# Peripherals.net
KiCad netlist of a schematic drawn in Altium Designer
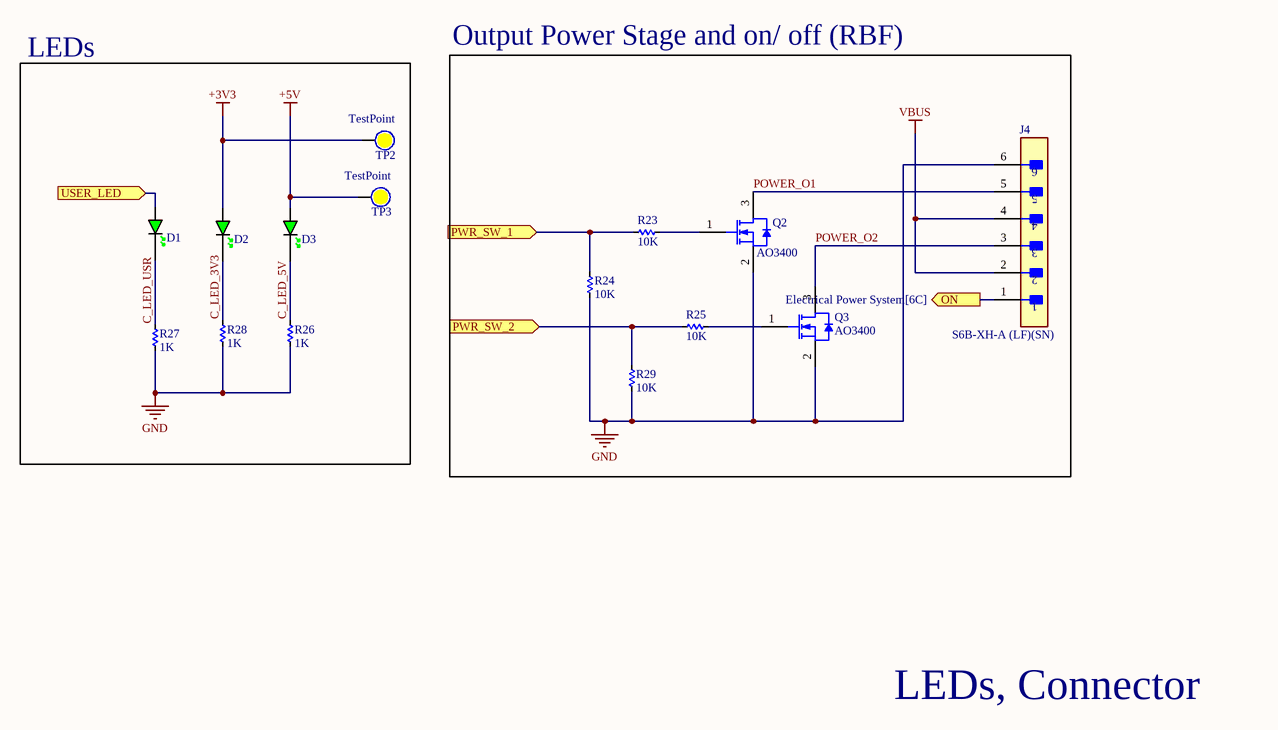
[diagram p0: Peripherals.SchDoc]

(export (version "E")
  (design (tool "Eeschema 10.0.6"))
  (components
    (comp (ref "D1")
      (value "GREEN")
      (footprint "LED_0603_GREEN")
      (description "LED 0603 GREEN SMD")
      (libsource (lib "Schematic-Lib-PhilsLab") (part "LED_0603_GREEN"))
    )
    (comp (ref "D2")
      (value "GREEN")
      (footprint "LED_0603_GREEN")
      (description "LED 0603 GREEN SMD")
      (libsource (lib "Schematic-Lib-PhilsLab") (part "LED_0603_GREEN"))
    )
    (comp (ref "D3")
      (value "GREEN")
      (footprint "LED_0603_GREEN")
      (description "LED 0603 GREEN SMD")
      (libsource (lib "Schematic-Lib-PhilsLab") (part "LED_0603_GREEN"))
    )
    (comp (ref "J4")
      (value "S6B-XH-A (LF)(SN)")
      (footprint "FP-S6B-XH-A_LF_SN-MFG")
      (description "CONN HEADER R/A 6POS 2.5MM")
      (libsource (lib "Altium Content Vault") (part "f2cb566baf1c37ab5a3b8e90bbeafd6"))
    )
    (comp (ref "Q2")
      (value "AO3400")
      (footprint "AO-SOT23-3_V")
      (description "N-channel Enhancement Mode Field-Effect Transistor; 5.8A/30V")
      (fields (field (name "MANUFACTURER") "Alpha and Omega"))
      (libsource (lib "Altium Content Vault") (part "AO-NEMOS-G1S2D3-3"))
    )
    (comp (ref "Q3")
      (value "AO3400")
      (footprint "AO-SOT23-3_V")
      (description "N-channel Enhancement Mode Field-Effect Transistor; 5.8A/30V")
      (fields (field (name "MANUFACTURER") "Alpha and Omega"))
      (libsource (lib "Altium Content Vault") (part "AO-NEMOS-G1S2D3-3"))
    )
    (comp (ref "R23")
      (value "10K")
      (footprint "RES-SMD-0805")
      (description "SMD")
      (fields
        (field (name "MANUFACTURER") "Generic Components")
        (field (name "PUBLISHER") "Altium Hobart Technology Centre")
      )
      (libsource (lib "Sang_library") (part "Res SMD"))
    )
    (comp (ref "R24")
      (value "10K")
      (footprint "RES-SMD-0805")
      (description "SMD")
      (fields
        (field (name "MANUFACTURER") "Generic Components")
        (field (name "PUBLISHER") "Altium Hobart Technology Centre")
      )
      (libsource (lib "Sang_library") (part "Res SMD"))
    )
    (comp (ref "R25")
      (value "10K")
      (footprint "RES-SMD-0805")
      (description "SMD")
      (fields
        (field (name "MANUFACTURER") "Generic Components")
        (field (name "PUBLISHER") "Altium Hobart Technology Centre")
      )
      (libsource (lib "Sang_library") (part "Res SMD"))
    )
    (comp (ref "R26")
      (value "1K")
      (footprint "RES-SMD-0805")
      (description "SMD")
      (fields
        (field (name "MANUFACTURER") "Generic Components")
        (field (name "PUBLISHER") "Altium Hobart Technology Centre")
      )
      (libsource (lib "") (part "Res SMD_1"))
    )
    (comp (ref "R27")
      (value "1K")
      (footprint "RES-SMD-0805")
      (description "SMD")
      (fields
        (field (name "MANUFACTURER") "Generic Components")
        (field (name "PUBLISHER") "Altium Hobart Technology Centre")
      )
      (libsource (lib "") (part "Res SMD_1"))
    )
    (comp (ref "R28")
      (value "1K")
      (footprint "RES-SMD-0805")
      (description "SMD")
      (fields
        (field (name "MANUFACTURER") "Generic Components")
        (field (name "PUBLISHER") "Altium Hobart Technology Centre")
      )
      (libsource (lib "") (part "Res SMD_1"))
    )
    (comp (ref "R29")
      (value "10K")
      (footprint "RES-SMD-0805")
      (description "SMD")
      (fields
        (field (name "MANUFACTURER") "Generic Components")
        (field (name "PUBLISHER") "Altium Hobart Technology Centre")
      )
      (libsource (lib "Sang_library") (part "Res SMD"))
    )
    (comp (ref "TP2")
      (value "TestPoint")
      (footprint "Test Point 1 MM")
      (description "Test Point")
      (libsource (lib "Sang_library") (part "Test Point"))
    )
    (comp (ref "TP3")
      (value "TestPoint")
      (footprint "Test Point 1 MM")
      (description "Test Point")
      (libsource (lib "Sang_library") (part "Test Point"))
    )
  )
  (nets
    (net (code "1") (name "+3V3") (class "Default")
      (node (ref "D2") (pin "A") (pinfunction "A_A") (pintype "passive"))
      (node (ref "TP2") (pin "0") (pinfunction "0_0") (pintype "passive"))
    )
    (net (code "2") (name "+5V") (class "Default")
      (node (ref "D3") (pin "A") (pinfunction "A_A") (pintype "passive"))
      (node (ref "TP3") (pin "0") (pinfunction "0_0") (pintype "passive"))
    )
    (net (code "3") (name "/C_LED_3V3") (class "Default")
      (node (ref "D2") (pin "K") (pinfunction "K_K") (pintype "passive"))
      (node (ref "R28") (pin "2") (pinfunction "2_2") (pintype "passive"))
    )
    (net (code "4") (name "/C_LED_5V") (class "Default")
      (node (ref "D3") (pin "K") (pinfunction "K_K") (pintype "passive"))
      (node (ref "R26") (pin "2") (pinfunction "2_2") (pintype "passive"))
    )
    (net (code "5") (name "/C_LED_USR") (class "Default")
      (node (ref "D1") (pin "K") (pinfunction "K_K") (pintype "passive"))
      (node (ref "R27") (pin "2") (pinfunction "2_2") (pintype "passive"))
    )
    (net (code "6") (name "/ON") (class "Default")
      (node (ref "J4") (pin "1") (pinfunction "1_1") (pintype "passive"))
    )
    (net (code "7") (name "/POWER_O1") (class "Default")
      (node (ref "J4") (pin "5") (pinfunction "5_5") (pintype "passive"))
      (node (ref "Q2") (pin "3") (pinfunction "D_3") (pintype "passive"))
    )
    (net (code "8") (name "/POWER_O2") (class "Default")
      (node (ref "J4") (pin "3") (pinfunction "3_3") (pintype "passive"))
      (node (ref "Q3") (pin "3") (pinfunction "D_3") (pintype "passive"))
    )
    (net (code "9") (name "/PWR_SW_1") (class "Default")
      (node (ref "R23") (pin "1") (pinfunction "1_1") (pintype "passive"))
      (node (ref "R24") (pin "1") (pinfunction "1_1") (pintype "passive"))
    )
    (net (code "10") (name "/PWR_SW_2") (class "Default")
      (node (ref "R25") (pin "1") (pinfunction "1_1") (pintype "passive"))
      (node (ref "R29") (pin "1") (pinfunction "1_1") (pintype "passive"))
    )
    (net (code "11") (name "/USER_LED") (class "Default")
      (node (ref "D1") (pin "A") (pinfunction "A_A") (pintype "passive"))
    )
    (net (code "12") (name "GND") (class "Default")
      (node (ref "J4") (pin "6") (pinfunction "6_6") (pintype "passive"))
      (node (ref "Q2") (pin "2") (pinfunction "S_2") (pintype "passive"))
      (node (ref "Q3") (pin "2") (pinfunction "S_2") (pintype "passive"))
      (node (ref "R24") (pin "2") (pinfunction "2_2") (pintype "passive"))
      (node (ref "R26") (pin "2") (pinfunction "2_2") (pintype "passive"))
      (node (ref "R27") (pin "2") (pinfunction "2_2") (pintype "passive"))
      (node (ref "R28") (pin "2") (pinfunction "2_2") (pintype "passive"))
      (node (ref "R29") (pin "2") (pinfunction "2_2") (pintype "passive"))
    )
    (net (code "13") (name "Net-(Q2-G)") (class "Default")
      (node (ref "Q2") (pin "1") (pinfunction "G_1") (pintype "passive"))
      (node (ref "R23") (pin "2") (pinfunction "2_2") (pintype "passive"))
    )
    (net (code "14") (name "Net-(Q3-G)") (class "Default")
      (node (ref "Q3") (pin "1") (pinfunction "G_1") (pintype "passive"))
      (node (ref "R25") (pin "2") (pinfunction "2_2") (pintype "passive"))
    )
    (net (code "15") (name "VBUS") (class "Default")
      (node (ref "J4") (pin "2") (pinfunction "2_2") (pintype "passive"))
      (node (ref "J4") (pin "4") (pinfunction "4_4") (pintype "passive"))
    )
  )
)
